# Communications_Board_-_Bottom.net
KiCad netlist of a schematic drawn in EAGLE
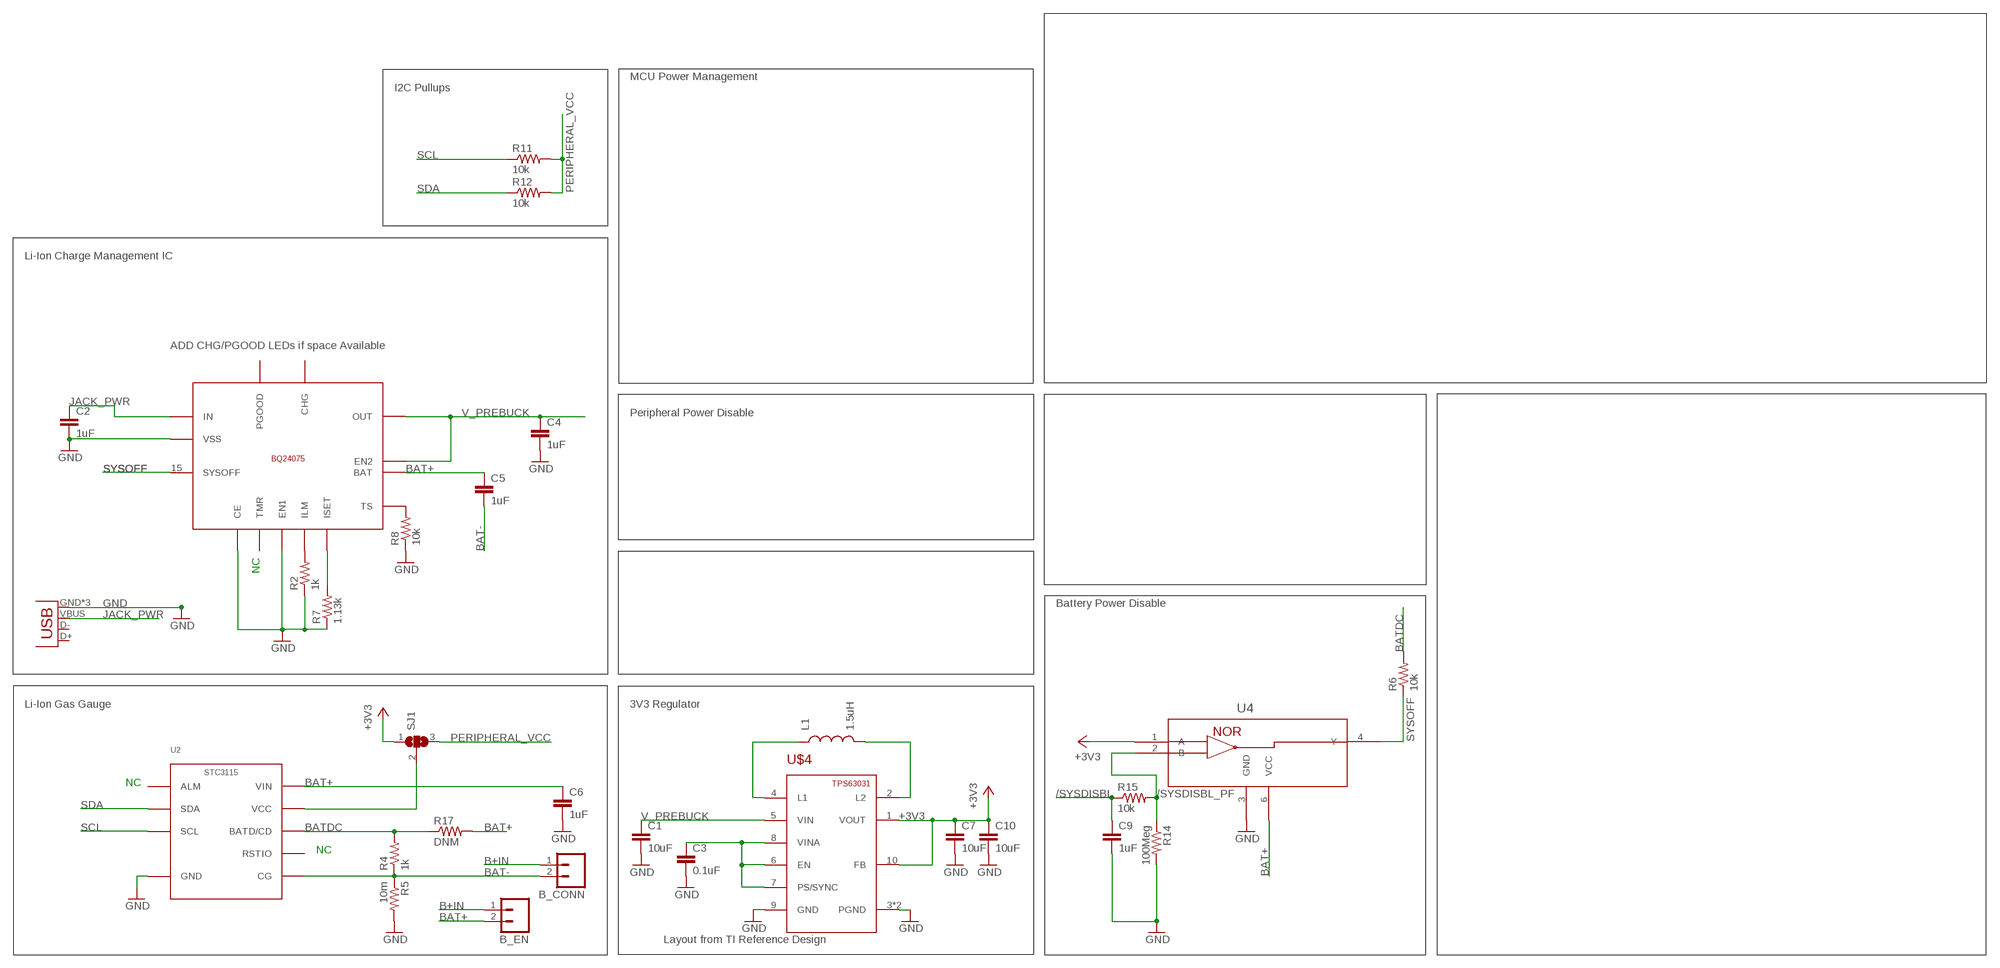
[diagram p0: schematic, sheet 1]
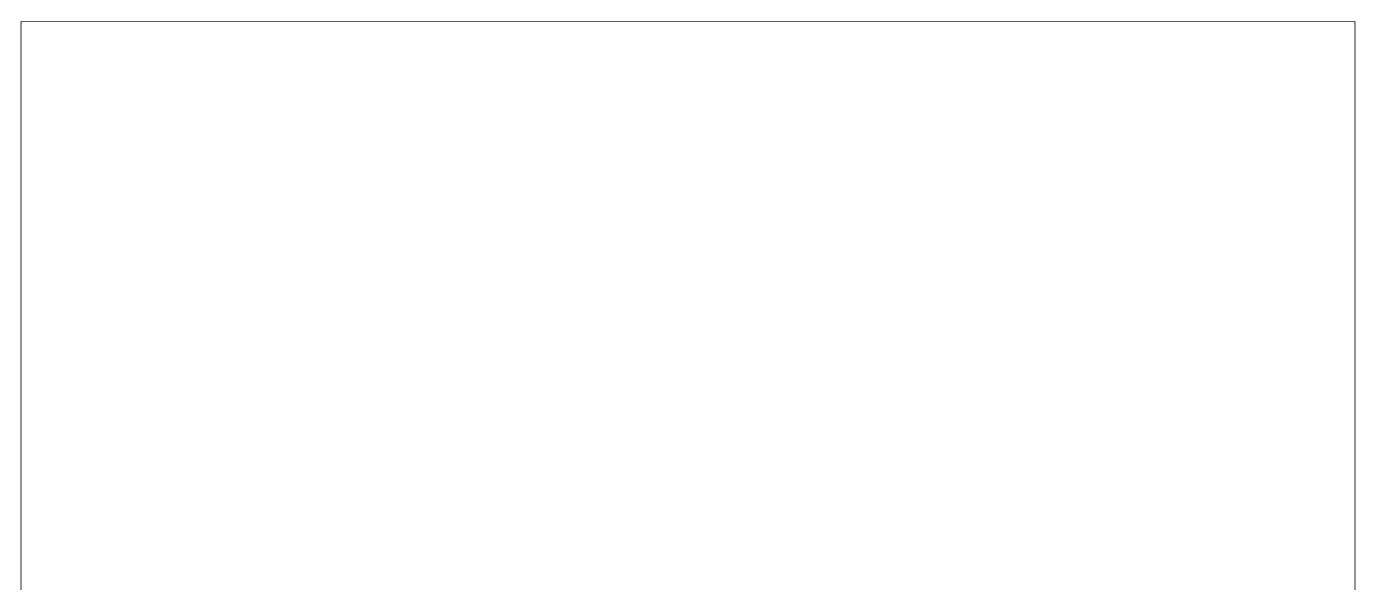
[diagram p1: schematic, sheet 2]
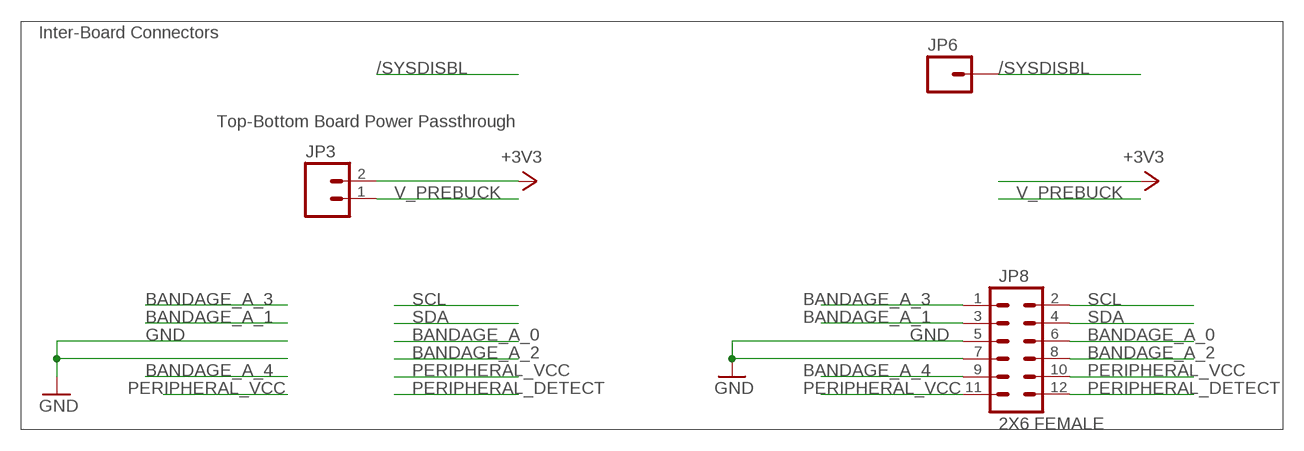
[diagram p2: schematic, sheet 3]

(export (version "E")
  (design (tool "Eeschema 10.0.6"))
  (components
    (comp (ref "B_CONN")
      (value "M02PTH")
      (footprint "eagle-import:1X02")
      (libsource (lib "eagle-import") (part "M02PTH"))
    )
    (comp (ref "B_EN")
      (value "M02PTH")
      (footprint "eagle-import:1X02")
      (libsource (lib "eagle-import") (part "M02PTH"))
    )
    (comp (ref "C1")
      (value "10uF")
      (footprint "eagle-import:0402-CAP")
      (libsource (lib "eagle-import") (part "SparkFun-Passives_CAP0402-CAP"))
    )
    (comp (ref "C2")
      (value "1uF")
      (footprint "eagle-import:0603-CAP")
      (libsource (lib "eagle-import") (part "CAP0603-CAP"))
    )
    (comp (ref "C3")
      (value "0.1uF")
      (footprint "eagle-import:0402-CAP")
      (libsource (lib "eagle-import") (part "SparkFun-Passives_CAP0402-CAP"))
    )
    (comp (ref "C4")
      (value "1uF")
      (footprint "eagle-import:0603-CAP")
      (libsource (lib "eagle-import") (part "CAP0603-CAP"))
    )
    (comp (ref "C5")
      (value "1uF")
      (footprint "eagle-import:0603-CAP")
      (libsource (lib "eagle-import") (part "CAP0603-CAP"))
    )
    (comp (ref "C6")
      (value "1uF")
      (footprint "eagle-import:0603-CAP")
      (libsource (lib "eagle-import") (part "CAP0603-CAP"))
    )
    (comp (ref "C7")
      (value "10uF")
      (footprint "eagle-import:0402-CAP")
      (libsource (lib "eagle-import") (part "SparkFun-Passives_CAP0402-CAP"))
    )
    (comp (ref "C9")
      (value "1uF")
      (footprint "eagle-import:0603-CAP")
      (libsource (lib "eagle-import") (part "SparkFun-Passives_CAP0603-CAP"))
    )
    (comp (ref "C10")
      (value "10uF")
      (footprint "eagle-import:0603-CAP")
      (libsource (lib "eagle-import") (part "SparkFun-Passives_CAP0603-CAP"))
    )
    (comp (ref "L1")
      (value "1.5uH")
      (footprint "eagle-import:IND1212")
      (libsource (lib "eagle-import") (part "INDUCTOR"))
    )
    (comp (ref "R2")
      (value "1k")
      (footprint "eagle-import:0603-RES")
      (libsource (lib "eagle-import") (part "RESISTOR0603-RES"))
    )
    (comp (ref "R4")
      (value "1k")
      (footprint "eagle-import:0603-RES")
      (libsource (lib "eagle-import") (part "RESISTOR0603-RES"))
    )
    (comp (ref "R5")
      (value "10m")
      (footprint "eagle-import:0603-RES")
      (libsource (lib "eagle-import") (part "RESISTOR0603-RES"))
    )
    (comp (ref "R6")
      (value "10k")
      (footprint "eagle-import:0603-RES")
      (libsource (lib "eagle-import") (part "RESISTOR0603-RES"))
    )
    (comp (ref "R7")
      (value "1.13k")
      (footprint "eagle-import:0603-RES")
      (libsource (lib "eagle-import") (part "RESISTOR0603-RES"))
    )
    (comp (ref "R8")
      (value "10k")
      (footprint "eagle-import:0603-RES")
      (libsource (lib "eagle-import") (part "RESISTOR0603-RES"))
    )
    (comp (ref "R11")
      (value "10k")
      (footprint "eagle-import:0603-RES")
      (libsource (lib "eagle-import") (part "RESISTOR0603-RES"))
    )
    (comp (ref "R12")
      (value "10k")
      (footprint "eagle-import:0603-RES")
      (libsource (lib "eagle-import") (part "RESISTOR0603-RES"))
    )
    (comp (ref "R14")
      (value "100Meg")
      (footprint "eagle-import:0603-RES")
      (libsource (lib "eagle-import") (part "RESISTOR0603-RES"))
    )
    (comp (ref "R15")
      (value "10k")
      (footprint "eagle-import:0603-RES")
      (libsource (lib "eagle-import") (part "RESISTOR0603-RES"))
    )
    (comp (ref "R17")
      (value "DNM")
      (footprint "eagle-import:0603-RES")
      (libsource (lib "eagle-import") (part "RESISTOR0603-RES"))
    )
    (comp (ref "SJ1")
      (value "SJ2W")
      (footprint "eagle-import:SJ_2")
      (libsource (lib "eagle-import") (part "SJ2W"))
    )
    (comp (ref "U$2")
      (value "BQ24075")
      (footprint "eagle-import:QFN16-3X3MM")
      (libsource (lib "eagle-import") (part "BQ24075"))
    )
    (comp (ref "U$4")
      (value "TPS63031")
      (footprint "eagle-import:SON-10")
      (libsource (lib "eagle-import") (part "TPS63031"))
    )
    (comp (ref "U2")
      (value "STC3115")
      (footprint "eagle-import:DFN10-2X3")
      (libsource (lib "eagle-import") (part "STC3115"))
    )
    (comp (ref "U4")
      (value "SN74AUP1G02_DSF_6")
      (footprint "eagle-import:DSF6")
      (fields
        (field (name "GENERIC_PART_NUMBER") "SN74AUP1G02")
        (field (name "MANUFACTURER") "Texas Instruments")
        (field (name "MANUFACTURER_PART_NUMBER") "sn74aup1g02_dsf_6")
      )
      (libsource (lib "eagle-import") (part "SN74AUP1G02_DSF_6"))
    )
    (comp (ref "X2")
      (value "USB-MICROB")
      (footprint "eagle-import:USB-MICROB")
      (libsource (lib "eagle-import") (part "USB-MICROB"))
    )
    (comp (ref "JP3")
      (value "M021X02_NO_SILK")
      (footprint "eagle-import:1X02_NO_SILK")
      (libsource (lib "eagle-import") (part "M021X02_NO_SILK"))
    )
    (comp (ref "JP6")
      (value "M01PTH")
      (footprint "eagle-import:1X01")
      (libsource (lib "eagle-import") (part "M01PTH"))
    )
    (comp (ref "JP8")
      (value "2X6 FEMALE")
      (footprint "eagle-import:2X6")
      (libsource (lib "eagle-import") (part "M06X2PTH_FEMALE"))
    )
  )
  (nets
    (net (code "1") (name "+3V3") (class "Default")
      (node (ref "C10") (pin "1") (pinfunction "1_1") (pintype "passive"))
      (node (ref "C7") (pin "1") (pinfunction "1_1") (pintype "passive"))
      (node (ref "JP3") (pin "2") (pinfunction "2_2") (pintype "passive"))
      (node (ref "SJ1") (pin "1") (pinfunction "1_1") (pintype "passive"))
      (node (ref "U$4") (pin "1") (pinfunction "VOUT_1") (pintype "bidirectional"))
      (node (ref "U$4") (pin "10") (pinfunction "FB_10") (pintype "bidirectional"))
      (node (ref "U4") (pin "1") (pinfunction "A_1") (pintype "input"))
    )
    (net (code "2") (name "B+IN") (class "Default")
      (node (ref "B_CONN") (pin "1") (pinfunction "1_1") (pintype "passive"))
      (node (ref "B_EN") (pin "1") (pinfunction "1_1") (pintype "passive"))
    )
    (net (code "3") (name "BANDAGE_A_0") (class "Default")
      (node (ref "JP8") (pin "6") (pinfunction "6_6") (pintype "passive"))
    )
    (net (code "4") (name "BANDAGE_A_1") (class "Default")
      (node (ref "JP8") (pin "3") (pinfunction "3_3") (pintype "passive"))
    )
    (net (code "5") (name "BANDAGE_A_2") (class "Default")
      (node (ref "JP8") (pin "8") (pinfunction "8_8") (pintype "passive"))
    )
    (net (code "6") (name "BANDAGE_A_3") (class "Default")
      (node (ref "JP8") (pin "1") (pinfunction "1_1") (pintype "passive"))
    )
    (net (code "7") (name "BANDAGE_A_4") (class "Default")
      (node (ref "JP8") (pin "9") (pinfunction "9_9") (pintype "passive"))
    )
    (net (code "8") (name "BAT+") (class "Default")
      (node (ref "B_EN") (pin "2") (pinfunction "2_2") (pintype "passive"))
      (node (ref "C5") (pin "1") (pinfunction "1_1") (pintype "passive"))
      (node (ref "C6") (pin "1") (pinfunction "1_1") (pintype "passive"))
      (node (ref "R17") (pin "2") (pinfunction "2_2") (pintype "passive"))
      (node (ref "U$2") (pin "2") (pinfunction "BAT_2") (pintype "bidirectional"))
      (node (ref "U$2") (pin "3") (pinfunction "BAT_3") (pintype "bidirectional"))
      (node (ref "U2") (pin "P10") (pinfunction "VIN_P10") (pintype "bidirectional"))
      (node (ref "U4") (pin "6") (pinfunction "VCC_6") (pintype "power_in"))
    )
    (net (code "9") (name "BAT-") (class "Default")
      (node (ref "B_CONN") (pin "2") (pinfunction "2_2") (pintype "passive"))
      (node (ref "C5") (pin "2") (pinfunction "2_2") (pintype "passive"))
      (node (ref "R4") (pin "1") (pinfunction "1_1") (pintype "passive"))
      (node (ref "R5") (pin "1") (pinfunction "1_1") (pintype "passive"))
      (node (ref "U2") (pin "P6") (pinfunction "CG_P6") (pintype "bidirectional"))
    )
    (net (code "10") (name "BATDC") (class "Default")
      (node (ref "R17") (pin "1") (pinfunction "1_1") (pintype "passive"))
      (node (ref "R4") (pin "2") (pinfunction "2_2") (pintype "passive"))
      (node (ref "R6") (pin "2") (pinfunction "2_2") (pintype "passive"))
      (node (ref "U2") (pin "P8") (pinfunction "BATD/CD_P8") (pintype "bidirectional"))
    )
    (net (code "11") (name "GND") (class "Default")
      (node (ref "C1") (pin "2") (pinfunction "2_2") (pintype "passive"))
      (node (ref "C10") (pin "2") (pinfunction "2_2") (pintype "passive"))
      (node (ref "C2") (pin "2") (pinfunction "2_2") (pintype "passive"))
      (node (ref "C3") (pin "2") (pinfunction "2_2") (pintype "passive"))
      (node (ref "C4") (pin "2") (pinfunction "2_2") (pintype "passive"))
      (node (ref "C6") (pin "2") (pinfunction "2_2") (pintype "passive"))
      (node (ref "C7") (pin "2") (pinfunction "2_2") (pintype "passive"))
      (node (ref "C9") (pin "2") (pinfunction "2_2") (pintype "passive"))
      (node (ref "JP8") (pin "5") (pinfunction "5_5") (pintype "passive"))
      (node (ref "JP8") (pin "7") (pinfunction "7_7") (pintype "passive"))
      (node (ref "R14") (pin "2") (pinfunction "2_2") (pintype "passive"))
      (node (ref "R2") (pin "1") (pinfunction "1_1") (pintype "passive"))
      (node (ref "R5") (pin "2") (pinfunction "2_2") (pintype "passive"))
      (node (ref "R7") (pin "1") (pinfunction "1_1") (pintype "passive"))
      (node (ref "R8") (pin "1") (pinfunction "1_1") (pintype "passive"))
      (node (ref "U$2") (pin "4") (pinfunction "CE_4") (pintype "bidirectional"))
      (node (ref "U$2") (pin "6") (pinfunction "EN1_6") (pintype "bidirectional"))
      (node (ref "U$2") (pin "8") (pinfunction "VSS_8") (pintype "bidirectional"))
      (node (ref "U$2") (pin "EXT") (pinfunction "VSS_EXT") (pintype "bidirectional"))
      (node (ref "U$4") (pin "3") (pinfunction "PGND_3") (pintype "bidirectional"))
      (node (ref "U$4") (pin "9") (pinfunction "GND_9") (pintype "bidirectional"))
      (node (ref "U$4") (pin "PAD") (pinfunction "PGND_PAD") (pintype "bidirectional"))
      (node (ref "U2") (pin "P5") (pinfunction "GND_P5") (pintype "bidirectional"))
      (node (ref "U4") (pin "3") (pinfunction "GND_3") (pintype "power_in"))
      (node (ref "X2") (pin "GND") (pinfunction "GND_GND") (pintype "bidirectional"))
      (node (ref "X2") (pin "MT1") (pinfunction "GND_MT1") (pintype "bidirectional"))
      (node (ref "X2") (pin "MT2") (pinfunction "GND_MT2") (pintype "bidirectional"))
    )
    (net (code "12") (name "JACK_PWR") (class "Default")
      (node (ref "C2") (pin "1") (pinfunction "1_1") (pintype "passive"))
      (node (ref "U$2") (pin "13") (pinfunction "IN_13") (pintype "bidirectional"))
      (node (ref "X2") (pin "VBUS") (pinfunction "VBUS_VBUS") (pintype "bidirectional"))
    )
    (net (code "13") (name "Net-(L1-1)") (class "Default")
      (node (ref "L1") (pin "P$1") (pinfunction "1_P$1") (pintype "passive"))
      (node (ref "U$4") (pin "4") (pinfunction "L1_4") (pintype "bidirectional"))
    )
    (net (code "14") (name "Net-(L1-2)") (class "Default")
      (node (ref "L1") (pin "P$2") (pinfunction "2_P$2") (pintype "passive"))
      (node (ref "U$4") (pin "2") (pinfunction "L2_2") (pintype "bidirectional"))
    )
    (net (code "15") (name "Net-(U$2-ILM)") (class "Default")
      (node (ref "R2") (pin "2") (pinfunction "2_2") (pintype "passive"))
      (node (ref "U$2") (pin "12") (pinfunction "ILM_12") (pintype "bidirectional"))
    )
    (net (code "16") (name "Net-(U$2-ISET)") (class "Default")
      (node (ref "R7") (pin "2") (pinfunction "2_2") (pintype "passive"))
      (node (ref "U$2") (pin "16") (pinfunction "ISET_16") (pintype "bidirectional"))
    )
    (net (code "17") (name "Net-(U$2-TS)") (class "Default")
      (node (ref "R8") (pin "2") (pinfunction "2_2") (pintype "passive"))
      (node (ref "U$2") (pin "1") (pinfunction "TS_1") (pintype "bidirectional"))
    )
    (net (code "18") (name "Net-(U$4-EN)") (class "Default")
      (node (ref "C3") (pin "1") (pinfunction "1_1") (pintype "passive"))
      (node (ref "U$4") (pin "6") (pinfunction "EN_6") (pintype "bidirectional"))
      (node (ref "U$4") (pin "7") (pinfunction "PS/SYNC_7") (pintype "bidirectional"))
      (node (ref "U$4") (pin "8") (pinfunction "VINA_8") (pintype "bidirectional"))
    )
    (net (code "19") (name "Net-(U2-VCC)") (class "Default")
      (node (ref "SJ1") (pin "2") (pinfunction "2_2") (pintype "passive"))
      (node (ref "U2") (pin "P9") (pinfunction "VCC_P9") (pintype "bidirectional"))
    )
    (net (code "20") (name "PERIPHERAL_DETECT") (class "Default")
      (node (ref "JP8") (pin "12") (pinfunction "12_12") (pintype "passive"))
    )
    (net (code "21") (name "PERIPHERAL_VCC") (class "Default")
      (node (ref "JP8") (pin "10") (pinfunction "10_10") (pintype "passive"))
      (node (ref "JP8") (pin "11") (pinfunction "11_11") (pintype "passive"))
      (node (ref "R11") (pin "2") (pinfunction "2_2") (pintype "passive"))
      (node (ref "R12") (pin "2") (pinfunction "2_2") (pintype "passive"))
      (node (ref "SJ1") (pin "3") (pinfunction "3_3") (pintype "passive"))
    )
    (net (code "22") (name "SCL") (class "Default")
      (node (ref "JP8") (pin "2") (pinfunction "2_2") (pintype "passive"))
      (node (ref "R11") (pin "1") (pinfunction "1_1") (pintype "passive"))
      (node (ref "U2") (pin "P3") (pinfunction "SCL_P3") (pintype "bidirectional"))
    )
    (net (code "23") (name "SDA") (class "Default")
      (node (ref "JP8") (pin "4") (pinfunction "4_4") (pintype "passive"))
      (node (ref "R12") (pin "1") (pinfunction "1_1") (pintype "passive"))
      (node (ref "U2") (pin "P2") (pinfunction "SDA_P2") (pintype "bidirectional"))
    )
    (net (code "24") (name "SYSOFF") (class "Default")
      (node (ref "R6") (pin "1") (pinfunction "1_1") (pintype "passive"))
      (node (ref "U$2") (pin "15") (pinfunction "SYSOFF_15") (pintype "bidirectional"))
      (node (ref "U4") (pin "4") (pinfunction "Y_4") (pintype "output"))
    )
    (net (code "25") (name "V_PREBUCK") (class "Default")
      (node (ref "C1") (pin "1") (pinfunction "1_1") (pintype "passive"))
      (node (ref "C4") (pin "1") (pinfunction "1_1") (pintype "passive"))
      (node (ref "JP3") (pin "1") (pinfunction "1_1") (pintype "passive"))
      (node (ref "U$2") (pin "10") (pinfunction "OUT_10") (pintype "power_in"))
      (node (ref "U$2") (pin "11") (pinfunction "OUT_11") (pintype "power_in"))
      (node (ref "U$2") (pin "5") (pinfunction "EN2_5") (pintype "bidirectional"))
      (node (ref "U$4") (pin "5") (pinfunction "VIN_5") (pintype "bidirectional"))
    )
    (net (code "26") (name "unconnected-(U$2-CHG-Pad9)") (class "Default")
      (node (ref "U$2") (pin "9") (pinfunction "CHG_9") (pintype "bidirectional"))
    )
    (net (code "27") (name "unconnected-(U$2-PGOOD-Pad7)") (class "Default")
      (node (ref "U$2") (pin "7") (pinfunction "PGOOD_7") (pintype "bidirectional"))
    )
    (net (code "28") (name "unconnected-(U$2-TMR-Pad14)") (class "Default")
      (node (ref "U$2") (pin "14") (pinfunction "TMR_14") (pintype "bidirectional"))
    )
    (net (code "29") (name "unconnected-(U2-ALM-PadP1)") (class "Default")
      (node (ref "U2") (pin "P1") (pinfunction "ALM_P1") (pintype "bidirectional"))
    )
    (net (code "30") (name "unconnected-(U2-RSTIO-PadP7)") (class "Default")
      (node (ref "U2") (pin "P7") (pinfunction "RSTIO_P7") (pintype "bidirectional"))
    )
    (net (code "31") (name "unconnected-(X2-PadD+)") (class "Default")
      (node (ref "X2") (pin "D+") (pinfunction "D+_D+") (pintype "bidirectional"))
    )
    (net (code "32") (name "unconnected-(X2-PadD-)") (class "Default")
      (node (ref "X2") (pin "D-") (pinfunction "D-_D-") (pintype "bidirectional"))
    )
    (net (code "33") (name "{slash}SYSDISBL") (class "Default")
      (node (ref "C9") (pin "1") (pinfunction "1_1") (pintype "passive"))
      (node (ref "JP6") (pin "1") (pinfunction "1_1") (pintype "passive"))
      (node (ref "R15") (pin "1") (pinfunction "1_1") (pintype "passive"))
    )
    (net (code "34") (name "{slash}SYSDISBL_PF") (class "Default")
      (node (ref "R14") (pin "1") (pinfunction "1_1") (pintype "passive"))
      (node (ref "R15") (pin "2") (pinfunction "2_2") (pintype "passive"))
      (node (ref "U4") (pin "2") (pinfunction "B_2") (pintype "input"))
    )
  )
)
